# sim.net
KiCad netlist of a schematic drawn in Altium Designer
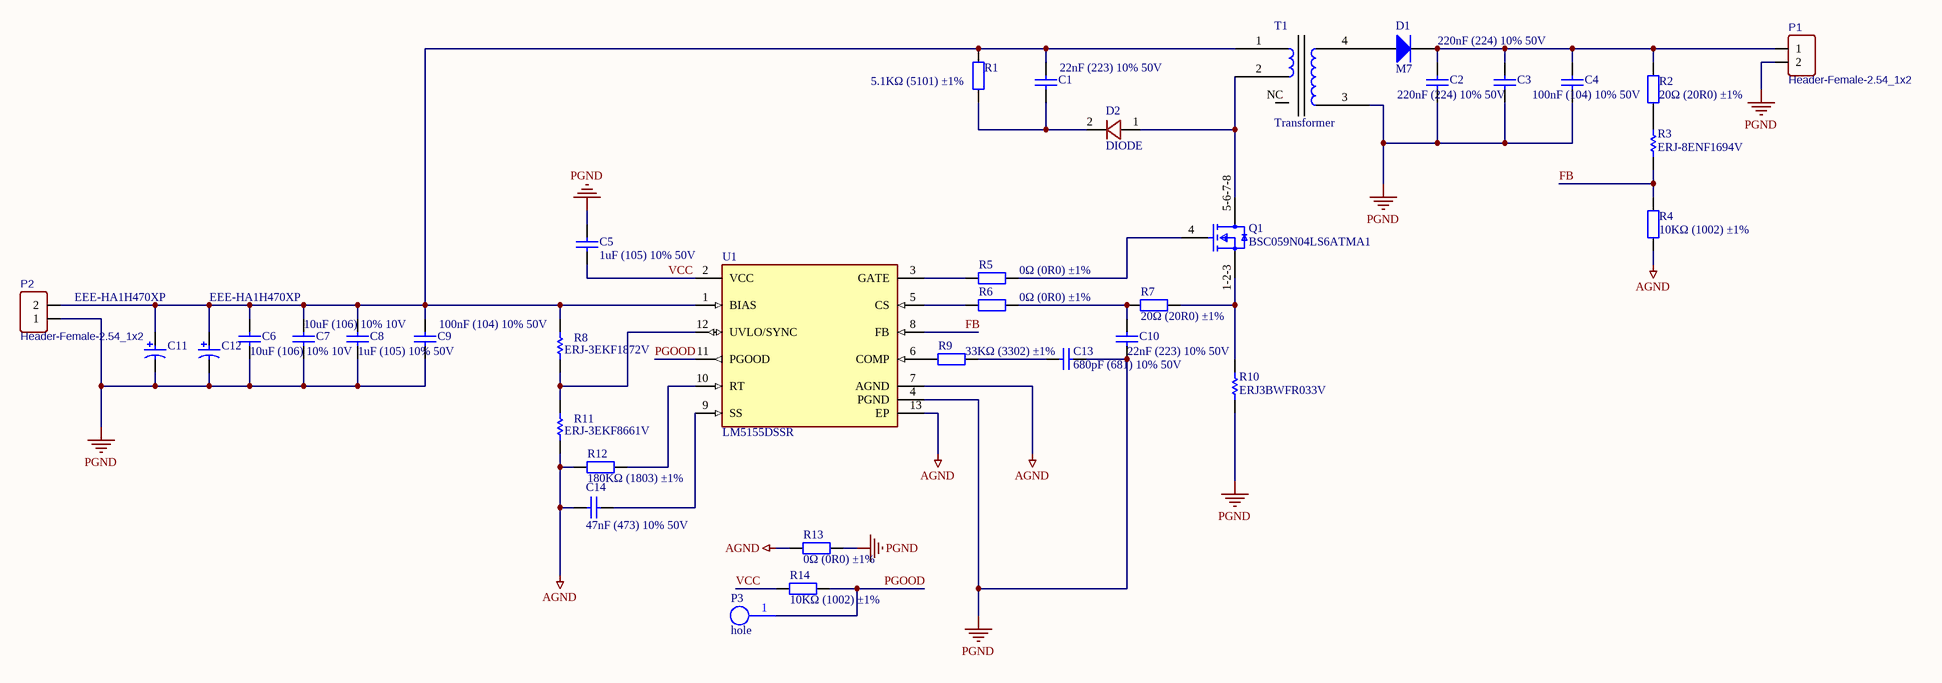
[diagram p0: sim.SchDoc]

(export (version "E")
  (design (tool "Eeschema 10.0.6"))
  (components
    (comp (ref "C1")
      (value "22nF (223) 10% 50V")
      (footprint "0603_C")
      (description "贴片电容")
      (libsource (lib "Cap") (part "0603 22nF (223) 10% 50V"))
    )
    (comp (ref "C2")
      (value "220nF (224) 10% 50V")
      (footprint "1206_C")
      (description "贴片电容")
      (libsource (lib "Cap") (part "1206 220nF (224) 10% 50V"))
    )
    (comp (ref "C3")
      (value "220nF (224) 10% 50V")
      (footprint "1206_C")
      (description "贴片电容")
      (libsource (lib "Cap") (part "1206 220nF (224) 10% 50V"))
    )
    (comp (ref "C4")
      (value "100nF (104) 10% 50V")
      (footprint "1206_C")
      (description "贴片电容")
      (libsource (lib "Cap") (part "1206 100nF (104) 10% 50V"))
    )
    (comp (ref "C5")
      (value "1uF (105) 10% 50V")
      (footprint "0603_C")
      (description "贴片电容")
      (libsource (lib "Cap") (part "0603 1uF (105) 10% 50V"))
    )
    (comp (ref "C6")
      (value "10uF (106) 10% 10V")
      (footprint "0603_C")
      (description "贴片电容")
      (libsource (lib "Cap") (part "0603 10uF (106) 10% 10V"))
    )
    (comp (ref "C7")
      (value "10uF (106) 10% 10V")
      (footprint "0603_C")
      (description "贴片电容")
      (libsource (lib "Cap") (part "0603 10uF (106) 10% 10V"))
    )
    (comp (ref "C8")
      (value "1uF (105) 10% 50V")
      (footprint "0603_C")
      (description "贴片电容")
      (libsource (lib "Cap") (part "0603 1uF (105) 10% 50V"))
    )
    (comp (ref "C9")
      (value "100nF (104) 10% 50V")
      (footprint "0603_C")
      (description "贴片电容")
      (libsource (lib "Cap") (part "0603 100nF (104) 10% 50V"))
    )
    (comp (ref "C10")
      (value "22nF (223) 10% 50V")
      (footprint "0603_C")
      (description "贴片电容")
      (libsource (lib "Cap") (part "0603 22nF (223) 10% 50V"))
    )
    (comp (ref "C11")
      (value "EEE-HA1H470XP")
      (footprint "PNSC-EEE-HA1H470XP-2_V")
      (fields (field (name "MANUFACTURER") "Panasonic"))
      (libsource (lib "Altium Content Vault") (part "PNSC-CAP-P-2"))
    )
    (comp (ref "C12")
      (value "EEE-HA1H470XP")
      (footprint "PNSC-EEE-HA1H470XP-2_V")
      (fields (field (name "MANUFACTURER") "Panasonic"))
      (libsource (lib "Altium Content Vault") (part "PNSC-CAP-P-2"))
    )
    (comp (ref "C13")
      (value "680pF (681) 10% 50V")
      (footprint "0603_C")
      (description "贴片电容")
      (libsource (lib "Cap") (part "0603 680pF (681) 10% 50V"))
    )
    (comp (ref "C14")
      (value "47nF (473) 10% 50V")
      (footprint "0603_C")
      (description "贴片电容")
      (libsource (lib "Cap") (part "0603 47nF (473) 10% 50V"))
    )
    (comp (ref "D1")
      (value "M7")
      (footprint "SMA(DO-214AC)_S1")
      (description "二极管")
      (libsource (lib "Diode") (part "SMA(DO-214AC) M7"))
    )
    (comp (ref "D2") (value "DIODE") (footprint "1N4150") (libsource (lib "Flyback") (part "1N4150")))
    (comp (ref "P1")
      (value "Header-Female-2.54_1x2")
      (footprint "HDR-TH_2P-P2.54-V-F")
      (fields
        (field (name "BOM_MANUFACTURER PART") "2.54-1*2PFemale")
        (field (name "BOM_SUPPLIER PART") "C49661")
      )
      (libsource (lib "Schlib1") (part "Header-Female-2.54_1x2"))
    )
    (comp (ref "P2")
      (value "Header-Female-2.54_1x2")
      (footprint "HDR-TH_2P-P2.54-V-F")
      (fields
        (field (name "BOM_MANUFACTURER PART") "2.54-1*2PFemale")
        (field (name "BOM_SUPPLIER PART") "C49661")
      )
      (libsource (lib "Schlib1") (part "Header-Female-2.54_1x2"))
    )
    (comp (ref "P3") (value "hole") (footprint "测试点") (libsource (lib "IN14") (part "测试点")))
    (comp (ref "Q1")
      (value "BSC059N04LS6ATMA1")
      (footprint "FP-PG-TDSON-8-MFG")
      (description "TRENCH <= 40V")
      (fields
        (field (name "MANUFACTURER") "Infineon")
        (field (name "OCTOPART") "https://octopart.com/bsc059n04ls6atma1-infineon-98039929")
      )
      (libsource (lib "Altium Content Vault") (part "1b0cff3a23bd3632373e77d40b07099"))
    )
    (comp (ref "R1")
      (value "5.1KΩ (5101) ±1%")
      (footprint "0603_R")
      (description "贴片电阻")
      (libsource (lib "RES") (part "0603 5.1KΩ (5101) 1%"))
    )
    (comp (ref "R2")
      (value "20Ω (20R0) ±1%")
      (footprint "0603_R")
      (description "贴片电阻")
      (libsource (lib "") (part "0603 20Ω (20R0) 1%_1"))
    )
    (comp (ref "R3")
      (value "ERJ-8ENF1694V")
      (footprint "RESC3216X70X50LL05T20")
      (fields (field (name "MANUFACTURER") "Panasonic"))
      (libsource (lib "Altium Content Vault") (part "RES"))
    )
    (comp (ref "R4")
      (value "10KΩ (1002) ±1%")
      (footprint "1206_R")
      (description "贴片电阻")
      (libsource (lib "RES") (part "1206 10KΩ (1002) 1%"))
    )
    (comp (ref "R5")
      (value "0Ω (0R0) ±1%")
      (footprint "0603_R")
      (description "贴片电阻")
      (libsource (lib "RES") (part "0603 0Ω (0R0) 1%"))
    )
    (comp (ref "R6")
      (value "0Ω (0R0) ±1%")
      (footprint "0603_R")
      (description "贴片电阻")
      (libsource (lib "RES") (part "0603 0Ω (0R0) 1%"))
    )
    (comp (ref "R7")
      (value "20Ω (20R0) ±1%")
      (footprint "0603_R")
      (description "贴片电阻")
      (libsource (lib "RES") (part "0603 20Ω (20R0) 1%"))
    )
    (comp (ref "R8")
      (value "ERJ-3EKF1872V")
      (footprint "RESC1608X55X30LL15T15")
      (fields (field (name "MANUFACTURER") "Panasonic"))
      (libsource (lib "Altium Content Vault") (part "RES"))
    )
    (comp (ref "R9")
      (value "33KΩ (3302) ±1%")
      (footprint "0603_R")
      (description "贴片电阻")
      (libsource (lib "RES") (part "0603 33KΩ (3302) 1%"))
    )
    (comp (ref "R10")
      (value "ERJ3BWFR033V")
      (footprint "RESC1608X55X30NL15T15")
      (fields (field (name "MANUFACTURER") "Panasonic"))
      (libsource (lib "Altium Content Vault") (part "RES"))
    )
    (comp (ref "R11")
      (value "ERJ-3EKF8661V")
      (footprint "RESC1608X55X30LL15T15")
      (fields (field (name "MANUFACTURER") "Panasonic"))
      (libsource (lib "Altium Content Vault") (part "RES"))
    )
    (comp (ref "R12")
      (value "180KΩ (1803) ±1%")
      (footprint "0603_R")
      (description "贴片电阻")
      (libsource (lib "RES") (part "0603 180KΩ (1803) 1%"))
    )
    (comp (ref "R13")
      (value "0Ω (0R0) ±1%")
      (footprint "0603_R")
      (description "贴片电阻")
      (libsource (lib "RES") (part "0603 0Ω (0R0) 1%"))
    )
    (comp (ref "R14")
      (value "10KΩ (1002) ±1%")
      (footprint "0603_R")
      (description "贴片电阻")
      (libsource (lib "RES") (part "0603 10KΩ (1002) 1%"))
    )
    (comp (ref "T1")
      (value "Transformer")
      (footprint "TTRN-060S")
      (libsource (lib "IN14") (part "TTRN-060S"))
    )
    (comp (ref "U1")
      (value "LM5155DSSR")
      (footprint "FP-DSS0012B-MFG")
      (description "POWER MANAGEMENT")
      (libsource (lib "Altium Content Vault") (part "0324625eb3cc54e9f007cb68cb6b815"))
    )
  )
  (nets
    (net (code "1") (name "/FB") (class "Default")
      (node (ref "R3") (pin "1") (pinfunction "1_1") (pintype "passive"))
      (node (ref "R4") (pin "2") (pinfunction "2_2") (pintype "passive"))
      (node (ref "U1") (pin "8") (pinfunction "FB_8") (pintype "input"))
    )
    (net (code "2") (name "/PGOOD") (class "Default")
      (node (ref "P3") (pin "1") (pinfunction "1_1") (pintype "passive"))
      (node (ref "R14") (pin "2") (pinfunction "2_2") (pintype "passive"))
      (node (ref "U1") (pin "11") (pinfunction "PGOOD_11") (pintype "output"))
    )
    (net (code "3") (name "/VCC") (class "Default")
      (node (ref "C5") (pin "1") (pinfunction "1_1") (pintype "passive"))
      (node (ref "R14") (pin "1") (pinfunction "1_1") (pintype "passive"))
      (node (ref "U1") (pin "2") (pinfunction "VCC_2") (pintype "power_in"))
    )
    (net (code "4") (name "AGND") (class "Default")
      (node (ref "C14") (pin "1") (pinfunction "1_1") (pintype "passive"))
      (node (ref "R11") (pin "1") (pinfunction "1_1") (pintype "passive"))
      (node (ref "R12") (pin "1") (pinfunction "1_1") (pintype "passive"))
      (node (ref "R13") (pin "1") (pinfunction "1_1") (pintype "passive"))
      (node (ref "R4") (pin "1") (pinfunction "1_1") (pintype "passive"))
      (node (ref "U1") (pin "13") (pinfunction "EP_13") (pintype "power_in"))
      (node (ref "U1") (pin "7") (pinfunction "AGND_7") (pintype "power_in"))
    )
    (net (code "5") (name "Net-(C1-Pad1)") (class "Default")
      (node (ref "C1") (pin "1") (pinfunction "1_1") (pintype "passive"))
      (node (ref "D2") (pin "2") (pinfunction "2_2") (pintype "passive"))
      (node (ref "R1") (pin "1") (pinfunction "1_1") (pintype "passive"))
    )
    (net (code "6") (name "Net-(C10-Pad2)") (class "Default")
      (node (ref "C10") (pin "2") (pinfunction "2_2") (pintype "passive"))
      (node (ref "R6") (pin "2") (pinfunction "2_2") (pintype "passive"))
      (node (ref "R7") (pin "1") (pinfunction "1_1") (pintype "passive"))
    )
    (net (code "7") (name "Net-(C13-Pad1)") (class "Default")
      (node (ref "C13") (pin "1") (pinfunction "1_1") (pintype "passive"))
      (node (ref "R9") (pin "2") (pinfunction "2_2") (pintype "passive"))
    )
    (net (code "8") (name "Net-(D1-A)") (class "Default")
      (node (ref "D1") (pin "1") (pinfunction "A_1") (pintype "passive"))
      (node (ref "T1") (pin "4") (pinfunction "3_4") (pintype "passive"))
    )
    (net (code "9") (name "Net-(D1-K)") (class "Default")
      (node (ref "C2") (pin "2") (pinfunction "2_2") (pintype "passive"))
      (node (ref "C3") (pin "2") (pinfunction "2_2") (pintype "passive"))
      (node (ref "C4") (pin "2") (pinfunction "2_2") (pintype "passive"))
      (node (ref "D1") (pin "2") (pinfunction "K_2") (pintype "passive"))
      (node (ref "P1") (pin "1") (pinfunction "1_1") (pintype "passive"))
      (node (ref "R2") (pin "2") (pinfunction "2_2") (pintype "passive"))
    )
    (net (code "10") (name "Net-(Q1-D)") (class "Default")
      (node (ref "D2") (pin "1") (pinfunction "1_1") (pintype "passive"))
      (node (ref "Q1") (pin "5-6-7-8") (pinfunction "D_5-6-7-8") (pintype "passive"))
      (node (ref "T1") (pin "2") (pinfunction "2_2") (pintype "passive"))
    )
    (net (code "11") (name "Net-(Q1-G)") (class "Default")
      (node (ref "Q1") (pin "4") (pinfunction "G_4") (pintype "passive"))
      (node (ref "R5") (pin "2") (pinfunction "2_2") (pintype "passive"))
    )
    (net (code "12") (name "Net-(Q1-S)") (class "Default")
      (node (ref "Q1") (pin "1-2-3") (pinfunction "S_1-2-3") (pintype "passive"))
      (node (ref "R10") (pin "2") (pinfunction "2_2") (pintype "passive"))
      (node (ref "R7") (pin "2") (pinfunction "2_2") (pintype "passive"))
    )
    (net (code "13") (name "Net-(R2-Pad1)") (class "Default")
      (node (ref "R2") (pin "1") (pinfunction "1_1") (pintype "passive"))
      (node (ref "R3") (pin "2") (pinfunction "2_2") (pintype "passive"))
    )
    (net (code "14") (name "Net-(U1-BIAS)") (class "Default")
      (node (ref "C1") (pin "2") (pinfunction "2_2") (pintype "passive"))
      (node (ref "C11") (pin "1") (pinfunction "1_1") (pintype "passive"))
      (node (ref "C12") (pin "1") (pinfunction "1_1") (pintype "passive"))
      (node (ref "C6") (pin "2") (pinfunction "2_2") (pintype "passive"))
      (node (ref "C7") (pin "2") (pinfunction "2_2") (pintype "passive"))
      (node (ref "C8") (pin "2") (pinfunction "2_2") (pintype "passive"))
      (node (ref "C9") (pin "2") (pinfunction "2_2") (pintype "passive"))
      (node (ref "P2") (pin "2") (pinfunction "2_2") (pintype "passive"))
      (node (ref "R1") (pin "2") (pinfunction "2_2") (pintype "passive"))
      (node (ref "R8") (pin "2") (pinfunction "2_2") (pintype "passive"))
      (node (ref "T1") (pin "1") (pinfunction "1_1") (pintype "passive"))
      (node (ref "U1") (pin "1") (pinfunction "BIAS_1") (pintype "input"))
    )
    (net (code "15") (name "Net-(U1-COMP)") (class "Default")
      (node (ref "R9") (pin "1") (pinfunction "1_1") (pintype "passive"))
      (node (ref "U1") (pin "6") (pinfunction "COMP_6") (pintype "input"))
    )
    (net (code "16") (name "Net-(U1-CS)") (class "Default")
      (node (ref "R6") (pin "1") (pinfunction "1_1") (pintype "passive"))
      (node (ref "U1") (pin "5") (pinfunction "CS_5") (pintype "input"))
    )
    (net (code "17") (name "Net-(U1-GATE)") (class "Default")
      (node (ref "R5") (pin "1") (pinfunction "1_1") (pintype "passive"))
      (node (ref "U1") (pin "3") (pinfunction "GATE_3") (pintype "passive"))
    )
    (net (code "18") (name "Net-(U1-RT)") (class "Default")
      (node (ref "R12") (pin "2") (pinfunction "2_2") (pintype "passive"))
      (node (ref "U1") (pin "10") (pinfunction "RT_10") (pintype "input"))
    )
    (net (code "19") (name "Net-(U1-SS)") (class "Default")
      (node (ref "C14") (pin "2") (pinfunction "2_2") (pintype "passive"))
      (node (ref "U1") (pin "9") (pinfunction "SS_9") (pintype "input"))
    )
    (net (code "20") (name "Net-(U1-UVLO{slash}SYNC)") (class "Default")
      (node (ref "R11") (pin "2") (pinfunction "2_2") (pintype "passive"))
      (node (ref "R8") (pin "1") (pinfunction "1_1") (pintype "passive"))
      (node (ref "U1") (pin "12") (pinfunction "UVLO/SYNC_12") (pintype "bidirectional"))
    )
    (net (code "21") (name "PGND") (class "Default")
      (node (ref "C10") (pin "1") (pinfunction "1_1") (pintype "passive"))
      (node (ref "C11") (pin "2") (pinfunction "2_2") (pintype "passive"))
      (node (ref "C12") (pin "2") (pinfunction "2_2") (pintype "passive"))
      (node (ref "C13") (pin "2") (pinfunction "2_2") (pintype "passive"))
      (node (ref "C2") (pin "1") (pinfunction "1_1") (pintype "passive"))
      (node (ref "C3") (pin "1") (pinfunction "1_1") (pintype "passive"))
      (node (ref "C4") (pin "1") (pinfunction "1_1") (pintype "passive"))
      (node (ref "C5") (pin "2") (pinfunction "2_2") (pintype "passive"))
      (node (ref "C6") (pin "1") (pinfunction "1_1") (pintype "passive"))
      (node (ref "C7") (pin "1") (pinfunction "1_1") (pintype "passive"))
      (node (ref "C8") (pin "1") (pinfunction "1_1") (pintype "passive"))
      (node (ref "C9") (pin "1") (pinfunction "1_1") (pintype "passive"))
      (node (ref "P1") (pin "2") (pinfunction "2_2") (pintype "passive"))
      (node (ref "P2") (pin "1") (pinfunction "1_1") (pintype "passive"))
      (node (ref "R10") (pin "1") (pinfunction "1_1") (pintype "passive"))
      (node (ref "R13") (pin "2") (pinfunction "2_2") (pintype "passive"))
      (node (ref "T1") (pin "3") (pinfunction "3_3") (pintype "passive"))
      (node (ref "U1") (pin "4") (pinfunction "PGND_4") (pintype "power_in"))
    )
    (net (code "22") (name "unconnected-(T1-6-PadNC)") (class "Default")
      (node (ref "T1") (pin "NC") (pinfunction "6_NC") (pintype "passive"))
    )
  )
)
